# microcontroller.net
KiCad netlist of a schematic drawn in Altium Designer
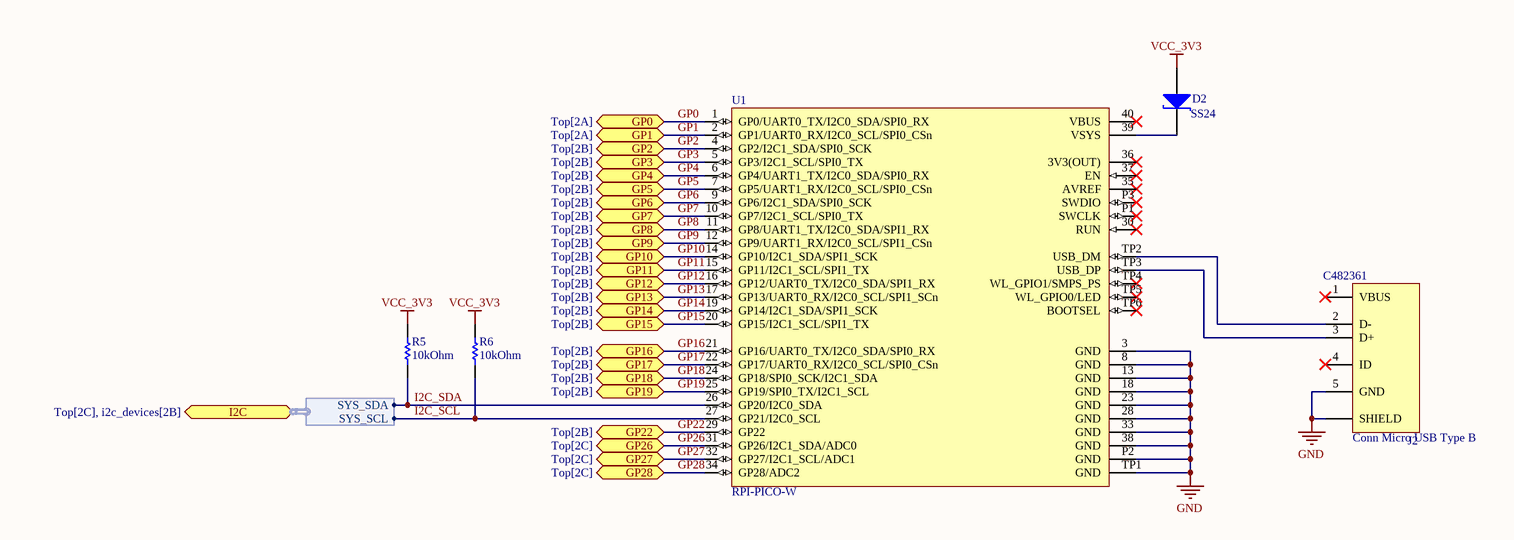
[diagram p0: microcontroller.SchDoc]

(export (version "E")
  (design (tool "Eeschema 10.0.6"))
  (components
    (comp (ref "D2")
      (value "SS24")
      (footprint "DO214AA")
      (description "40V Single 500mV@2A 2A DO-214AA Schottky Barrier Diodes (SBD) ROHS")
      (libsource (lib "MY_LIB") (part "Dioda prostownicza Schottky"))
    )
    (comp (ref "J2")
      (value "10118193-0001LF")
      (footprint "10118193-0001LF")
      (description "Conn Micro USB Type B RCP 5 POS 0.65mm Solder RA SMD 5 Terminal 1 Port T/R")
      (fields (field (name "NAME") "Conn Micro USB Type B") (field (name "SUPPLIER PART NUMBER 1") "C482361"))
      (libsource (lib "altium_conclusive_library") (part "10118193-0001LF"))
    )
    (comp (ref "R5")
      (value "0603 10kOhm 1%")
      (footprint "RES_0603")
      (description "Generic Resistor SMD")
      (fields (field (name "RESISTANCE") "10kOhm"))
      (libsource (lib "MY_LIB") (part "Resistor SMD_1"))
    )
    (comp (ref "R6")
      (value "0603 10kOhm 1%")
      (footprint "RES_0603")
      (description "Generic Resistor SMD")
      (fields (field (name "RESISTANCE") "10kOhm"))
      (libsource (lib "MY_LIB") (part "Resistor SMD_1"))
    )
    (comp (ref "U1")
      (value "RPI-PICO-W")
      (footprint "RPI-PICO-W")
      (description "Raspberry Pi Pico W - RP2040 ARM Cortex M0+ CYW43439")
      (fields
        (field (name "MANUFACTURER") "Raspberry Pi Foundation")
        (field (name "MANUFACTURER PART NO") "SC0915")
      )
      (libsource (lib "MY_LIB") (part "RPI-PICO-W"))
    )
  )
  (nets
    (net (code "2") (name "/GP0") (class "Default")
      (node (ref "U1") (pin "1") (pinfunction "GP0/UART0_TX/I2C0_SDA/SPI0_RX_1") (pintype "bidirectional"))
    )
    (net (code "3") (name "/GP1") (class "Default")
      (node (ref "U1") (pin "2") (pinfunction "GP1/UART0_RX/I2C0_SCL/SPI0_CSn_2") (pintype "bidirectional"))
    )
    (net (code "4") (name "/GP2") (class "Default")
      (node (ref "U1") (pin "4") (pinfunction "GP2/I2C1_SDA/SPI0_SCK_4") (pintype "bidirectional"))
    )
    (net (code "5") (name "/GP3") (class "Default")
      (node (ref "U1") (pin "5") (pinfunction "GP3/I2C1_SCL/SPI0_TX_5") (pintype "bidirectional"))
    )
    (net (code "6") (name "/GP4") (class "Default")
      (node (ref "U1") (pin "6") (pinfunction "GP4/UART1_TX/I2C0_SDA/SPI0_RX_6") (pintype "bidirectional"))
    )
    (net (code "7") (name "/GP5") (class "Default")
      (node (ref "U1") (pin "7") (pinfunction "GP5/UART1_RX/I2C0_SCL/SPI0_CSn_7") (pintype "bidirectional"))
    )
    (net (code "8") (name "/GP6") (class "Default")
      (node (ref "U1") (pin "9") (pinfunction "GP6/I2C1_SDA/SPI0_SCK_9") (pintype "bidirectional"))
    )
    (net (code "9") (name "/GP7") (class "Default")
      (node (ref "U1") (pin "10") (pinfunction "GP7/I2C1_SCL/SPI0_TX_10") (pintype "bidirectional"))
    )
    (net (code "10") (name "/GP8") (class "Default")
      (node (ref "U1") (pin "11") (pinfunction "GP8/UART1_TX/I2C0_SDA/SPI1_RX_11") (pintype "bidirectional"))
    )
    (net (code "11") (name "/GP9") (class "Default")
      (node (ref "U1") (pin "12") (pinfunction "GP9/UART1_RX/I2C0_SCL/SPI1_CSn_12") (pintype "bidirectional"))
    )
    (net (code "12") (name "/GP10") (class "Default")
      (node (ref "U1") (pin "14") (pinfunction "GP10/I2C1_SDA/SPI1_SCK_14") (pintype "bidirectional"))
    )
    (net (code "13") (name "/GP11") (class "Default")
      (node (ref "U1") (pin "15") (pinfunction "GP11/I2C1_SCL/SPI1_TX_15") (pintype "bidirectional"))
    )
    (net (code "14") (name "/GP12") (class "Default")
      (node (ref "U1") (pin "16") (pinfunction "GP12/UART0_TX/I2C0_SDA/SPI1_RX_16") (pintype "bidirectional"))
    )
    (net (code "15") (name "/GP13") (class "Default")
      (node (ref "U1") (pin "17") (pinfunction "GP13/UART0_RX/I2C0_SCL/SPI1_SCn_17") (pintype "bidirectional"))
    )
    (net (code "16") (name "/GP14") (class "Default")
      (node (ref "U1") (pin "19") (pinfunction "GP14/I2C1_SDA/SPI1_SCK_19") (pintype "bidirectional"))
    )
    (net (code "17") (name "/GP15") (class "Default")
      (node (ref "U1") (pin "20") (pinfunction "GP15/I2C1_SCL/SPI1_TX_20") (pintype "bidirectional"))
    )
    (net (code "18") (name "/GP16") (class "Default")
      (node (ref "U1") (pin "21") (pinfunction "GP16/UART0_TX/I2C0_SDA/SPI0_RX_21") (pintype "bidirectional"))
    )
    (net (code "19") (name "/GP17") (class "Default")
      (node (ref "U1") (pin "22") (pinfunction "GP17/UART0_RX/I2C0_SCL/SPI0_CSn_22") (pintype "bidirectional"))
    )
    (net (code "20") (name "/GP18") (class "Default")
      (node (ref "U1") (pin "24") (pinfunction "GP18/SPI0_SCK/I2C1_SDA_24") (pintype "bidirectional"))
    )
    (net (code "21") (name "/GP19") (class "Default")
      (node (ref "U1") (pin "25") (pinfunction "GP19/SPI0_TX/I2C1_SCL_25") (pintype "bidirectional"))
    )
    (net (code "22") (name "/GP22") (class "Default")
      (node (ref "U1") (pin "29") (pinfunction "GP22_29") (pintype "bidirectional"))
    )
    (net (code "23") (name "/GP26") (class "Default")
      (node (ref "U1") (pin "31") (pinfunction "GP26/I2C1_SDA/ADC0_31") (pintype "bidirectional"))
    )
    (net (code "24") (name "/GP27") (class "Default")
      (node (ref "U1") (pin "32") (pinfunction "GP27/I2C1_SCL/ADC1_32") (pintype "bidirectional"))
    )
    (net (code "25") (name "/GP28") (class "Default")
      (node (ref "U1") (pin "34") (pinfunction "GP28/ADC2_34") (pintype "bidirectional"))
    )
    (net (code "26") (name "/I2C_SCL") (class "Default")
      (node (ref "R6") (pin "2") (pinfunction "2_2") (pintype "passive"))
      (node (ref "U1") (pin "27") (pinfunction "GP21/I2C0_SCL_27") (pintype "bidirectional"))
    )
    (net (code "27") (name "/I2C_SDA") (class "Default")
      (node (ref "R5") (pin "2") (pinfunction "2_2") (pintype "passive"))
      (node (ref "U1") (pin "26") (pinfunction "GP20/I2C0_SDA_26") (pintype "bidirectional"))
    )
    (net (code "29") (name "GND") (class "Default")
      (node (ref "J2") (pin "5") (pinfunction "GND_5") (pintype "passive"))
      (node (ref "J2") (pin "S1") (pinfunction "SHIELD_S1") (pintype "passive"))
      (node (ref "U1") (pin "13") (pinfunction "GND_13") (pintype "power_in"))
      (node (ref "U1") (pin "18") (pinfunction "GND_18") (pintype "power_in"))
      (node (ref "U1") (pin "23") (pinfunction "GND_23") (pintype "power_in"))
      (node (ref "U1") (pin "28") (pinfunction "GND_28") (pintype "power_in"))
      (node (ref "U1") (pin "3") (pinfunction "GND_3") (pintype "power_in"))
      (node (ref "U1") (pin "33") (pinfunction "GND_33") (pintype "power_in"))
      (node (ref "U1") (pin "38") (pinfunction "GND_38") (pintype "power_in"))
      (node (ref "U1") (pin "8") (pinfunction "GND_8") (pintype "power_in"))
      (node (ref "U1") (pin "P2") (pinfunction "GND_P2") (pintype "power_in"))
      (node (ref "U1") (pin "TP1") (pinfunction "GND_TP1") (pintype "power_in"))
    )
    (net (code "30") (name "Net-(J2-D+)") (class "Default")
      (node (ref "J2") (pin "3") (pinfunction "D+_3") (pintype "passive"))
      (node (ref "U1") (pin "TP3") (pinfunction "USB_DP_TP3") (pintype "bidirectional"))
    )
    (net (code "31") (name "Net-(J2-D-)") (class "Default")
      (node (ref "J2") (pin "2") (pinfunction "D-_2") (pintype "passive"))
      (node (ref "U1") (pin "TP2") (pinfunction "USB_DM_TP2") (pintype "bidirectional"))
    )
    (net (code "32") (name "Net-(U1-VSYS)") (class "Default")
      (node (ref "D2") (pin "K") (pinfunction "K_K") (pintype "passive"))
      (node (ref "U1") (pin "39") (pinfunction "VSYS_39") (pintype "power_in"))
    )
    (net (code "33") (name "VCC_3V3") (class "Default")
      (node (ref "D2") (pin "A") (pinfunction "A_A") (pintype "passive"))
      (node (ref "R5") (pin "1") (pinfunction "1_1") (pintype "passive"))
      (node (ref "R6") (pin "1") (pinfunction "1_1") (pintype "passive"))
    )
    (net (code "34") (name "unconnected-(J2-ID-Pad4)") (class "Default")
      (node (ref "J2") (pin "4") (pinfunction "ID_4") (pintype "passive+no_connect"))
    )
    (net (code "35") (name "unconnected-(J2-VBUS-Pad1)") (class "Default")
      (node (ref "J2") (pin "1") (pinfunction "VBUS_1") (pintype "passive+no_connect"))
    )
    (net (code "36") (name "unconnected-(U1-3V3(OUT)-Pad36)") (class "Default")
      (node (ref "U1") (pin "36") (pinfunction "3V3(OUT)_36") (pintype "power_in+no_connect"))
    )
    (net (code "37") (name "unconnected-(U1-AVREF-Pad35)") (class "Default")
      (node (ref "U1") (pin "35") (pinfunction "AVREF_35") (pintype "power_in+no_connect"))
    )
    (net (code "38") (name "unconnected-(U1-BOOTSEL-PadTP6)") (class "Default")
      (node (ref "U1") (pin "TP6") (pinfunction "BOOTSEL_TP6") (pintype "bidirectional+no_connect"))
    )
    (net (code "39") (name "unconnected-(U1-EN-Pad37)") (class "Default")
      (node (ref "U1") (pin "37") (pinfunction "EN_37") (pintype "input+no_connect"))
    )
    (net (code "40") (name "unconnected-(U1-RUN-Pad30)") (class "Default")
      (node (ref "U1") (pin "30") (pinfunction "RUN_30") (pintype "input+no_connect"))
    )
    (net (code "41") (name "unconnected-(U1-SWCLK-PadP1)") (class "Default")
      (node (ref "U1") (pin "P1") (pinfunction "SWCLK_P1") (pintype "bidirectional+no_connect"))
    )
    (net (code "42") (name "unconnected-(U1-SWDIO-PadP3)") (class "Default")
      (node (ref "U1") (pin "P3") (pinfunction "SWDIO_P3") (pintype "bidirectional+no_connect"))
    )
    (net (code "43") (name "unconnected-(U1-VBUS-Pad40)") (class "Default")
      (node (ref "U1") (pin "40") (pinfunction "VBUS_40") (pintype "power_in+no_connect"))
    )
    (net (code "44") (name "unconnected-(U1-WL_GPIO0{slash}LED-PadTP5)") (class "Default")
      (node (ref "U1") (pin "TP5") (pinfunction "WL_GPIO0/LED_TP5") (pintype "bidirectional+no_connect"))
    )
    (net (code "45") (name "unconnected-(U1-WL_GPIO1{slash}SMPS_PS-PadTP4)") (class "Default")
      (node (ref "U1") (pin "TP4") (pinfunction "WL_GPIO1/SMPS_PS_TP4") (pintype "bidirectional+no_connect"))
    )
  )
)
